# 6x5keyboard_v2_groovy.net
KiCad netlist of a schematic drawn in EAGLE
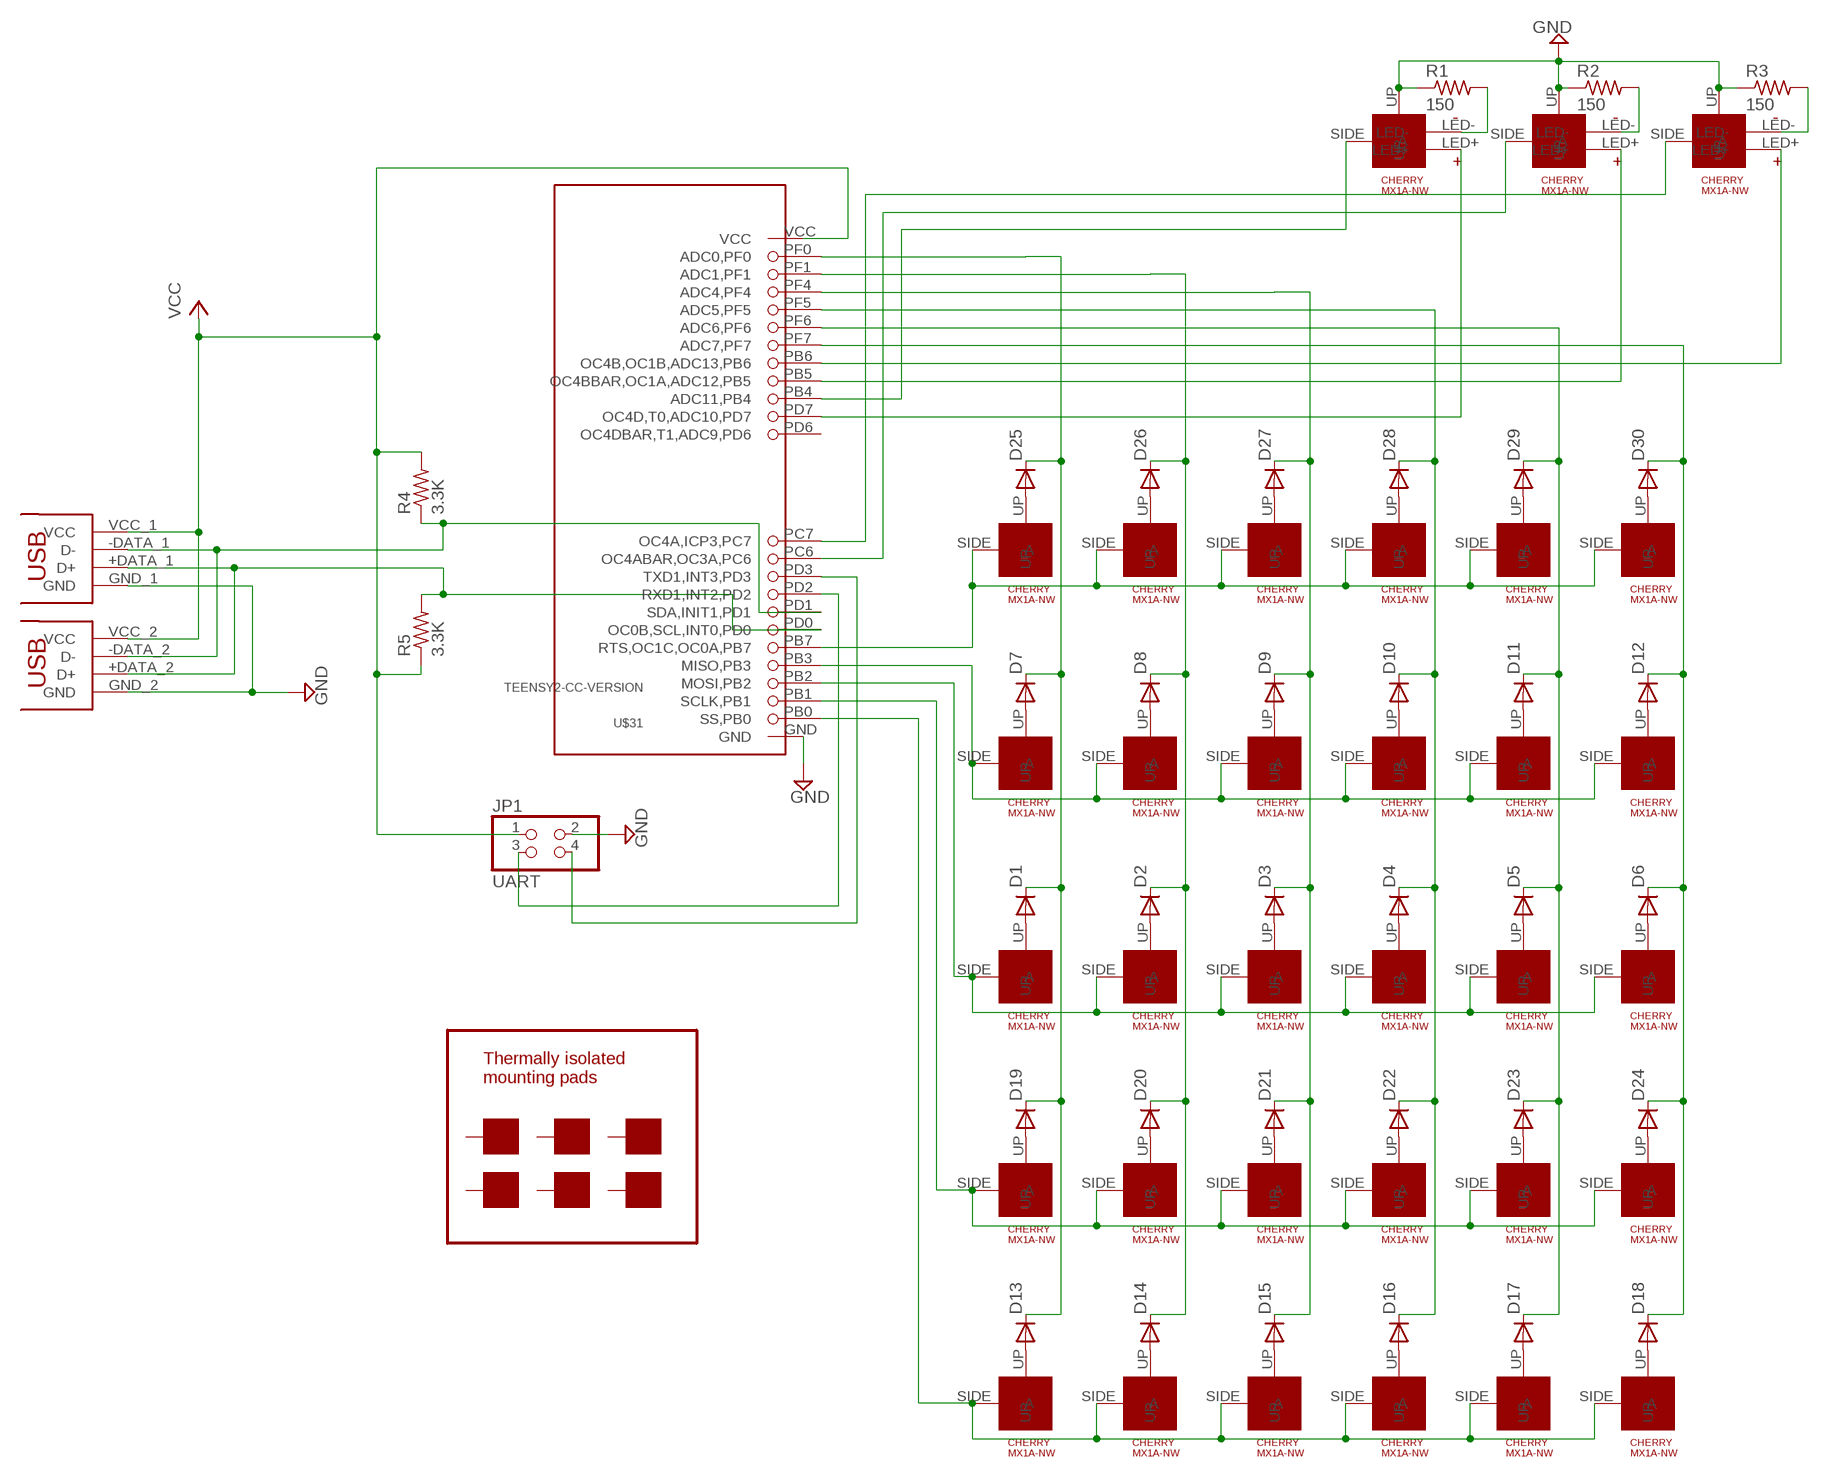
[diagram p0: schematic, sheet 1]

(export (version "E")
  (design (tool "Eeschema 10.0.6"))
  (components
    (comp (ref "D1")
      (value "1N4148DO35-7")
      (footprint "eagle-import:DO35-7")
      (libsource (lib "eagle-import") (part "1N4148DO35-7"))
    )
    (comp (ref "D2")
      (value "1N4148DO35-7")
      (footprint "eagle-import:DO35-7")
      (libsource (lib "eagle-import") (part "1N4148DO35-7"))
    )
    (comp (ref "D3")
      (value "1N4148DO35-7")
      (footprint "eagle-import:DO35-7")
      (libsource (lib "eagle-import") (part "1N4148DO35-7"))
    )
    (comp (ref "D4")
      (value "1N4148DO35-7")
      (footprint "eagle-import:DO35-7")
      (libsource (lib "eagle-import") (part "1N4148DO35-7"))
    )
    (comp (ref "D5")
      (value "1N4148DO35-7")
      (footprint "eagle-import:DO35-7")
      (libsource (lib "eagle-import") (part "1N4148DO35-7"))
    )
    (comp (ref "D6")
      (value "1N4148DO35-7")
      (footprint "eagle-import:DO35-7")
      (libsource (lib "eagle-import") (part "1N4148DO35-7"))
    )
    (comp (ref "D7")
      (value "1N4148DO35-7")
      (footprint "eagle-import:DO35-7")
      (libsource (lib "eagle-import") (part "1N4148DO35-7"))
    )
    (comp (ref "D8")
      (value "1N4148DO35-7")
      (footprint "eagle-import:DO35-7")
      (libsource (lib "eagle-import") (part "1N4148DO35-7"))
    )
    (comp (ref "D9")
      (value "1N4148DO35-7")
      (footprint "eagle-import:DO35-7")
      (libsource (lib "eagle-import") (part "1N4148DO35-7"))
    )
    (comp (ref "D10")
      (value "1N4148DO35-7")
      (footprint "eagle-import:DO35-7")
      (libsource (lib "eagle-import") (part "1N4148DO35-7"))
    )
    (comp (ref "D11")
      (value "1N4148DO35-7")
      (footprint "eagle-import:DO35-7")
      (libsource (lib "eagle-import") (part "1N4148DO35-7"))
    )
    (comp (ref "D12")
      (value "1N4148DO35-7")
      (footprint "eagle-import:DO35-7")
      (libsource (lib "eagle-import") (part "1N4148DO35-7"))
    )
    (comp (ref "D13")
      (value "1N4148DO35-7")
      (footprint "eagle-import:DO35-7")
      (libsource (lib "eagle-import") (part "1N4148DO35-7"))
    )
    (comp (ref "D14")
      (value "1N4148DO35-7")
      (footprint "eagle-import:DO35-7")
      (libsource (lib "eagle-import") (part "1N4148DO35-7"))
    )
    (comp (ref "D15")
      (value "1N4148DO35-7")
      (footprint "eagle-import:DO35-7")
      (libsource (lib "eagle-import") (part "1N4148DO35-7"))
    )
    (comp (ref "D16")
      (value "1N4148DO35-7")
      (footprint "eagle-import:DO35-7")
      (libsource (lib "eagle-import") (part "1N4148DO35-7"))
    )
    (comp (ref "D17")
      (value "1N4148DO35-7")
      (footprint "eagle-import:DO35-7")
      (libsource (lib "eagle-import") (part "1N4148DO35-7"))
    )
    (comp (ref "D18")
      (value "1N4148DO35-7")
      (footprint "eagle-import:DO35-7")
      (libsource (lib "eagle-import") (part "1N4148DO35-7"))
    )
    (comp (ref "D19")
      (value "1N4148DO35-7")
      (footprint "eagle-import:DO35-7")
      (libsource (lib "eagle-import") (part "1N4148DO35-7"))
    )
    (comp (ref "D20")
      (value "1N4148DO35-7")
      (footprint "eagle-import:DO35-7")
      (libsource (lib "eagle-import") (part "1N4148DO35-7"))
    )
    (comp (ref "D21")
      (value "1N4148DO35-7")
      (footprint "eagle-import:DO35-7")
      (libsource (lib "eagle-import") (part "1N4148DO35-7"))
    )
    (comp (ref "D22")
      (value "1N4148DO35-7")
      (footprint "eagle-import:DO35-7")
      (libsource (lib "eagle-import") (part "1N4148DO35-7"))
    )
    (comp (ref "D23")
      (value "1N4148DO35-7")
      (footprint "eagle-import:DO35-7")
      (libsource (lib "eagle-import") (part "1N4148DO35-7"))
    )
    (comp (ref "D24")
      (value "1N4148DO35-7")
      (footprint "eagle-import:DO35-7")
      (libsource (lib "eagle-import") (part "1N4148DO35-7"))
    )
    (comp (ref "D25")
      (value "1N4148DO35-7")
      (footprint "eagle-import:DO35-7")
      (libsource (lib "eagle-import") (part "1N4148DO35-7"))
    )
    (comp (ref "D26")
      (value "1N4148DO35-7")
      (footprint "eagle-import:DO35-7")
      (libsource (lib "eagle-import") (part "1N4148DO35-7"))
    )
    (comp (ref "D27")
      (value "1N4148DO35-7")
      (footprint "eagle-import:DO35-7")
      (libsource (lib "eagle-import") (part "1N4148DO35-7"))
    )
    (comp (ref "D28")
      (value "1N4148DO35-7")
      (footprint "eagle-import:DO35-7")
      (libsource (lib "eagle-import") (part "1N4148DO35-7"))
    )
    (comp (ref "D29")
      (value "1N4148DO35-7")
      (footprint "eagle-import:DO35-7")
      (libsource (lib "eagle-import") (part "1N4148DO35-7"))
    )
    (comp (ref "D30")
      (value "1N4148DO35-7")
      (footprint "eagle-import:DO35-7")
      (libsource (lib "eagle-import") (part "1N4148DO35-7"))
    )
    (comp (ref "JP1")
      (value "UART")
      (footprint "eagle-import:2X02")
      (libsource (lib "eagle-import") (part "PINHD-2X2"))
    )
    (comp (ref "R1")
      (value "150")
      (footprint "eagle-import:0207_10")
      (libsource (lib "eagle-import") (part "R-US_0207/10"))
    )
    (comp (ref "R2")
      (value "150")
      (footprint "eagle-import:0207_10")
      (libsource (lib "eagle-import") (part "R-US_0207/10"))
    )
    (comp (ref "R3")
      (value "150")
      (footprint "eagle-import:0207_10")
      (libsource (lib "eagle-import") (part "R-US_0207/10"))
    )
    (comp (ref "R4")
      (value "3.3K")
      (footprint "eagle-import:0207_10")
      (libsource (lib "eagle-import") (part "resistor_R-US_0207/10"))
    )
    (comp (ref "R5")
      (value "3.3K")
      (footprint "eagle-import:0207_10")
      (libsource (lib "eagle-import") (part "resistor_R-US_0207/10"))
    )
    (comp (ref "U$1")
      (value "CHERRY-MX1A-E1NW")
      (footprint "eagle-import:CHERRYMX-NN")
      (libsource (lib "eagle-import") (part "CHERRY-MX1A-E1NW"))
    )
    (comp (ref "U$2")
      (value "CHERRY-MX1A-E1NW")
      (footprint "eagle-import:CHERRYMX-NN")
      (libsource (lib "eagle-import") (part "CHERRY-MX1A-E1NW"))
    )
    (comp (ref "U$3")
      (value "CHERRY-MX1A-E1NW")
      (footprint "eagle-import:CHERRYMX-NN")
      (libsource (lib "eagle-import") (part "CHERRY-MX1A-E1NW"))
    )
    (comp (ref "U$4")
      (value "CHERRY-MX1A-E1NW")
      (footprint "eagle-import:CHERRYMX-NN")
      (libsource (lib "eagle-import") (part "CHERRY-MX1A-E1NW"))
    )
    (comp (ref "U$5")
      (value "CHERRY-MX1A-E1NW")
      (footprint "eagle-import:CHERRYMX-NN")
      (libsource (lib "eagle-import") (part "CHERRY-MX1A-E1NW"))
    )
    (comp (ref "U$6")
      (value "CHERRY-MX1A-E1NW")
      (footprint "eagle-import:CHERRYMX-NN")
      (libsource (lib "eagle-import") (part "CHERRY-MX1A-E1NW"))
    )
    (comp (ref "U$7")
      (value "CHERRY-MX1A-E1NW")
      (footprint "eagle-import:CHERRYMX-NN")
      (libsource (lib "eagle-import") (part "CHERRY-MX1A-E1NW"))
    )
    (comp (ref "U$8")
      (value "CHERRY-MX1A-E1NW")
      (footprint "eagle-import:CHERRYMX-NN")
      (libsource (lib "eagle-import") (part "CHERRY-MX1A-E1NW"))
    )
    (comp (ref "U$9")
      (value "CHERRY-MX1A-E1NW")
      (footprint "eagle-import:CHERRYMX-NN")
      (libsource (lib "eagle-import") (part "CHERRY-MX1A-E1NW"))
    )
    (comp (ref "U$10")
      (value "CHERRY-MX1A-E1NW")
      (footprint "eagle-import:CHERRYMX-NN")
      (libsource (lib "eagle-import") (part "CHERRY-MX1A-E1NW"))
    )
    (comp (ref "U$11")
      (value "CHERRY-MX1A-E1NW")
      (footprint "eagle-import:CHERRYMX-NN")
      (libsource (lib "eagle-import") (part "CHERRY-MX1A-E1NW"))
    )
    (comp (ref "U$12")
      (value "CHERRY-MX1A-E1NW")
      (footprint "eagle-import:CHERRYMX-NN")
      (libsource (lib "eagle-import") (part "CHERRY-MX1A-E1NW"))
    )
    (comp (ref "U$13")
      (value "CHERRY-MX1A-E1NW")
      (footprint "eagle-import:CHERRYMX-NN")
      (libsource (lib "eagle-import") (part "CHERRY-MX1A-E1NW"))
    )
    (comp (ref "U$14")
      (value "CHERRY-MX1A-E1NW")
      (footprint "eagle-import:CHERRYMX-NN")
      (libsource (lib "eagle-import") (part "CHERRY-MX1A-E1NW"))
    )
    (comp (ref "U$15")
      (value "CHERRY-MX1A-E1NW")
      (footprint "eagle-import:CHERRYMX-NN")
      (libsource (lib "eagle-import") (part "CHERRY-MX1A-E1NW"))
    )
    (comp (ref "U$16")
      (value "CHERRY-MX1A-E1NW")
      (footprint "eagle-import:CHERRYMX-NN")
      (libsource (lib "eagle-import") (part "CHERRY-MX1A-E1NW"))
    )
    (comp (ref "U$17")
      (value "CHERRY-MX1A-E1NW")
      (footprint "eagle-import:CHERRYMX-NN")
      (libsource (lib "eagle-import") (part "CHERRY-MX1A-E1NW"))
    )
    (comp (ref "U$18")
      (value "CHERRY-MX1A-E1NW")
      (footprint "eagle-import:CHERRYMX-NN")
      (libsource (lib "eagle-import") (part "CHERRY-MX1A-E1NW"))
    )
    (comp (ref "U$19")
      (value "CHERRY-MX1A-E1NW")
      (footprint "eagle-import:CHERRYMX-NN")
      (libsource (lib "eagle-import") (part "CHERRY-MX1A-E1NW"))
    )
    (comp (ref "U$20")
      (value "CHERRY-MX1A-E1NW")
      (footprint "eagle-import:CHERRYMX-NN")
      (libsource (lib "eagle-import") (part "CHERRY-MX1A-E1NW"))
    )
    (comp (ref "U$21")
      (value "CHERRY-MX1A-E1NW")
      (footprint "eagle-import:CHERRYMX-NN")
      (libsource (lib "eagle-import") (part "CHERRY-MX1A-E1NW"))
    )
    (comp (ref "U$22")
      (value "CHERRY-MX1A-E1NW")
      (footprint "eagle-import:CHERRYMX-NN")
      (libsource (lib "eagle-import") (part "CHERRY-MX1A-E1NW"))
    )
    (comp (ref "U$23")
      (value "CHERRY-MX1A-E1NW")
      (footprint "eagle-import:CHERRYMX-NN")
      (libsource (lib "eagle-import") (part "CHERRY-MX1A-E1NW"))
    )
    (comp (ref "U$24")
      (value "CHERRY-MX1A-E1NW")
      (footprint "eagle-import:CHERRYMX-NN")
      (libsource (lib "eagle-import") (part "CHERRY-MX1A-E1NW"))
    )
    (comp (ref "U$25")
      (value "CHERRY-MX1A-E1NW")
      (footprint "eagle-import:CHERRYMX-NN")
      (libsource (lib "eagle-import") (part "CHERRY-MX1A-E1NW"))
    )
    (comp (ref "U$26")
      (value "CHERRY-MX1A-E1NW")
      (footprint "eagle-import:CHERRYMX-NN")
      (libsource (lib "eagle-import") (part "CHERRY-MX1A-E1NW"))
    )
    (comp (ref "U$27")
      (value "CHERRY-MX1A-E1NW")
      (footprint "eagle-import:CHERRYMX-NN")
      (libsource (lib "eagle-import") (part "CHERRY-MX1A-E1NW"))
    )
    (comp (ref "U$28")
      (value "CHERRY-MX1A-E1NW")
      (footprint "eagle-import:CHERRYMX-NN")
      (libsource (lib "eagle-import") (part "CHERRY-MX1A-E1NW"))
    )
    (comp (ref "U$29")
      (value "CHERRY-MX1A-E1NW")
      (footprint "eagle-import:CHERRYMX-NN")
      (libsource (lib "eagle-import") (part "CHERRY-MX1A-E1NW"))
    )
    (comp (ref "U$30")
      (value "CHERRY-MX1A-E1NW")
      (footprint "eagle-import:CHERRYMX-NN")
      (libsource (lib "eagle-import") (part "CHERRY-MX1A-E1NW"))
    )
    (comp (ref "U$31")
      (value "TEENSY2-CC-VERSION")
      (footprint "eagle-import:TEENSY2")
      (libsource (lib "eagle-import") (part "TEENSY2-CC-VERSION"))
    )
    (comp (ref "U$32")
      (value "CHERRY-MX1A-E1NW-LED")
      (footprint "eagle-import:CHERRYMX-NN-LED")
      (libsource (lib "eagle-import") (part "CHERRY-MX1A-E1NW-LED"))
    )
    (comp (ref "U$33")
      (value "CHERRY-MX1A-E1NW-LED")
      (footprint "eagle-import:CHERRYMX-NN-LED")
      (libsource (lib "eagle-import") (part "CHERRY-MX1A-E1NW-LED"))
    )
    (comp (ref "U$34")
      (value "CHERRY-MX1A-E1NW-LED")
      (footprint "eagle-import:CHERRYMX-NN-LED")
      (libsource (lib "eagle-import") (part "CHERRY-MX1A-E1NW-LED"))
    )
    (comp (ref "U$35")
      (value "DUAL-USB-A")
      (footprint "eagle-import:DUAL-USB-A")
      (libsource (lib "eagle-import") (part "DUAL-USB-A"))
    )
    (comp (ref "U$36")
      (value "MOUNTING-PAD")
      (footprint "eagle-import:MOUNTING-PAD")
      (libsource (lib "eagle-import") (part "MOUNTING-PAD"))
    )
    (comp (ref "U$37")
      (value "MOUNTING-PAD")
      (footprint "eagle-import:MOUNTING-PAD")
      (libsource (lib "eagle-import") (part "MOUNTING-PAD"))
    )
    (comp (ref "U$38")
      (value "MOUNTING-PAD")
      (footprint "eagle-import:MOUNTING-PAD")
      (libsource (lib "eagle-import") (part "MOUNTING-PAD"))
    )
    (comp (ref "U$39")
      (value "MOUNTING-PAD")
      (footprint "eagle-import:MOUNTING-PAD")
      (libsource (lib "eagle-import") (part "MOUNTING-PAD"))
    )
    (comp (ref "U$40")
      (value "MOUNTING-PAD")
      (footprint "eagle-import:MOUNTING-PAD")
      (libsource (lib "eagle-import") (part "MOUNTING-PAD"))
    )
    (comp (ref "U$41")
      (value "MOUNTING-PAD")
      (footprint "eagle-import:MOUNTING-PAD")
      (libsource (lib "eagle-import") (part "MOUNTING-PAD"))
    )
  )
  (nets
    (net (code "1") (name "GND") (class "Default")
      (node (ref "JP1") (pin "2") (pinfunction "2_2") (pintype "passive"))
      (node (ref "R1") (pin "1") (pinfunction "1_1") (pintype "passive"))
      (node (ref "R2") (pin "1") (pinfunction "1_1") (pintype "passive"))
      (node (ref "R3") (pin "1") (pinfunction "1_1") (pintype "passive"))
      (node (ref "U$31") (pin "GND") (pinfunction "GND_GND") (pintype "power_in"))
      (node (ref "U$32") (pin "UP") (pinfunction "UP_UP") (pintype "bidirectional"))
      (node (ref "U$33") (pin "UP") (pinfunction "UP_UP") (pintype "bidirectional"))
      (node (ref "U$34") (pin "UP") (pinfunction "UP_UP") (pintype "bidirectional"))
      (node (ref "U$35") (pin "GND_1") (pinfunction "GND_GND_1") (pintype "bidirectional"))
      (node (ref "U$35") (pin "GND_2") (pinfunction "GND_GND_2") (pintype "bidirectional"))
    )
    (net (code "2") (name "Net-(D1-PadA)") (class "Default")
      (node (ref "D1") (pin "A") (pinfunction "A_A") (pintype "passive"))
      (node (ref "U$2") (pin "UP") (pinfunction "UP_UP") (pintype "bidirectional"))
    )
    (net (code "3") (name "Net-(D2-PadA)") (class "Default")
      (node (ref "D2") (pin "A") (pinfunction "A_A") (pintype "passive"))
      (node (ref "U$1") (pin "UP") (pinfunction "UP_UP") (pintype "bidirectional"))
    )
    (net (code "4") (name "Net-(D3-PadA)") (class "Default")
      (node (ref "D3") (pin "A") (pinfunction "A_A") (pintype "passive"))
      (node (ref "U$3") (pin "UP") (pinfunction "UP_UP") (pintype "bidirectional"))
    )
    (net (code "5") (name "Net-(D4-PadA)") (class "Default")
      (node (ref "D4") (pin "A") (pinfunction "A_A") (pintype "passive"))
      (node (ref "U$4") (pin "UP") (pinfunction "UP_UP") (pintype "bidirectional"))
    )
    (net (code "6") (name "Net-(D5-PadA)") (class "Default")
      (node (ref "D5") (pin "A") (pinfunction "A_A") (pintype "passive"))
      (node (ref "U$5") (pin "UP") (pinfunction "UP_UP") (pintype "bidirectional"))
    )
    (net (code "7") (name "Net-(D6-PadA)") (class "Default")
      (node (ref "D6") (pin "A") (pinfunction "A_A") (pintype "passive"))
      (node (ref "U$6") (pin "UP") (pinfunction "UP_UP") (pintype "bidirectional"))
    )
    (net (code "8") (name "Net-(D7-PadA)") (class "Default")
      (node (ref "D7") (pin "A") (pinfunction "A_A") (pintype "passive"))
      (node (ref "U$7") (pin "UP") (pinfunction "UP_UP") (pintype "bidirectional"))
    )
    (net (code "9") (name "Net-(D8-PadA)") (class "Default")
      (node (ref "D8") (pin "A") (pinfunction "A_A") (pintype "passive"))
      (node (ref "U$8") (pin "UP") (pinfunction "UP_UP") (pintype "bidirectional"))
    )
    (net (code "10") (name "Net-(D9-PadA)") (class "Default")
      (node (ref "D9") (pin "A") (pinfunction "A_A") (pintype "passive"))
      (node (ref "U$9") (pin "UP") (pinfunction "UP_UP") (pintype "bidirectional"))
    )
    (net (code "11") (name "Net-(D10-PadA)") (class "Default")
      (node (ref "D10") (pin "A") (pinfunction "A_A") (pintype "passive"))
      (node (ref "U$10") (pin "UP") (pinfunction "UP_UP") (pintype "bidirectional"))
    )
    (net (code "12") (name "Net-(D11-PadA)") (class "Default")
      (node (ref "D11") (pin "A") (pinfunction "A_A") (pintype "passive"))
      (node (ref "U$11") (pin "UP") (pinfunction "UP_UP") (pintype "bidirectional"))
    )
    (net (code "13") (name "Net-(D12-PadA)") (class "Default")
      (node (ref "D12") (pin "A") (pinfunction "A_A") (pintype "passive"))
      (node (ref "U$12") (pin "UP") (pinfunction "UP_UP") (pintype "bidirectional"))
    )
    (net (code "14") (name "Net-(D13-PadA)") (class "Default")
      (node (ref "D13") (pin "A") (pinfunction "A_A") (pintype "passive"))
      (node (ref "U$13") (pin "UP") (pinfunction "UP_UP") (pintype "bidirectional"))
    )
    (net (code "15") (name "Net-(D14-PadA)") (class "Default")
      (node (ref "D14") (pin "A") (pinfunction "A_A") (pintype "passive"))
      (node (ref "U$14") (pin "UP") (pinfunction "UP_UP") (pintype "bidirectional"))
    )
    (net (code "16") (name "Net-(D15-PadA)") (class "Default")
      (node (ref "D15") (pin "A") (pinfunction "A_A") (pintype "passive"))
      (node (ref "U$15") (pin "UP") (pinfunction "UP_UP") (pintype "bidirectional"))
    )
    (net (code "17") (name "Net-(D16-PadA)") (class "Default")
      (node (ref "D16") (pin "A") (pinfunction "A_A") (pintype "passive"))
      (node (ref "U$16") (pin "UP") (pinfunction "UP_UP") (pintype "bidirectional"))
    )
    (net (code "18") (name "Net-(D17-PadA)") (class "Default")
      (node (ref "D17") (pin "A") (pinfunction "A_A") (pintype "passive"))
      (node (ref "U$17") (pin "UP") (pinfunction "UP_UP") (pintype "bidirectional"))
    )
    (net (code "19") (name "Net-(D18-PadA)") (class "Default")
      (node (ref "D18") (pin "A") (pinfunction "A_A") (pintype "passive"))
      (node (ref "U$18") (pin "UP") (pinfunction "UP_UP") (pintype "bidirectional"))
    )
    (net (code "20") (name "Net-(D19-PadA)") (class "Default")
      (node (ref "D19") (pin "A") (pinfunction "A_A") (pintype "passive"))
      (node (ref "U$19") (pin "UP") (pinfunction "UP_UP") (pintype "bidirectional"))
    )
    (net (code "21") (name "Net-(D20-PadA)") (class "Default")
      (node (ref "D20") (pin "A") (pinfunction "A_A") (pintype "passive"))
      (node (ref "U$20") (pin "UP") (pinfunction "UP_UP") (pintype "bidirectional"))
    )
    (net (code "22") (name "Net-(D21-PadA)") (class "Default")
      (node (ref "D21") (pin "A") (pinfunction "A_A") (pintype "passive"))
      (node (ref "U$21") (pin "UP") (pinfunction "UP_UP") (pintype "bidirectional"))
    )
    (net (code "23") (name "Net-(D22-PadA)") (class "Default")
      (node (ref "D22") (pin "A") (pinfunction "A_A") (pintype "passive"))
      (node (ref "U$22") (pin "UP") (pinfunction "UP_UP") (pintype "bidirectional"))
    )
    (net (code "24") (name "Net-(D23-PadA)") (class "Default")
      (node (ref "D23") (pin "A") (pinfunction "A_A") (pintype "passive"))
      (node (ref "U$23") (pin "UP") (pinfunction "UP_UP") (pintype "bidirectional"))
    )
    (net (code "25") (name "Net-(D24-PadA)") (class "Default")
      (node (ref "D24") (pin "A") (pinfunction "A_A") (pintype "passive"))
      (node (ref "U$24") (pin "UP") (pinfunction "UP_UP") (pintype "bidirectional"))
    )
    (net (code "26") (name "Net-(D25-PadA)") (class "Default")
      (node (ref "D25") (pin "A") (pinfunction "A_A") (pintype "passive"))
      (node (ref "U$25") (pin "UP") (pinfunction "UP_UP") (pintype "bidirectional"))
    )
    (net (code "27") (name "Net-(D26-PadA)") (class "Default")
      (node (ref "D26") (pin "A") (pinfunction "A_A") (pintype "passive"))
      (node (ref "U$26") (pin "UP") (pinfunction "UP_UP") (pintype "bidirectional"))
    )
    (net (code "28") (name "Net-(D27-PadA)") (class "Default")
      (node (ref "D27") (pin "A") (pinfunction "A_A") (pintype "passive"))
      (node (ref "U$27") (pin "UP") (pinfunction "UP_UP") (pintype "bidirectional"))
    )
    (net (code "29") (name "Net-(D28-PadA)") (class "Default")
      (node (ref "D28") (pin "A") (pinfunction "A_A") (pintype "passive"))
      (node (ref "U$28") (pin "UP") (pinfunction "UP_UP") (pintype "bidirectional"))
    )
    (net (code "30") (name "Net-(D29-PadA)") (class "Default")
      (node (ref "D29") (pin "A") (pinfunction "A_A") (pintype "passive"))
      (node (ref "U$29") (pin "UP") (pinfunction "UP_UP") (pintype "bidirectional"))
    )
    (net (code "31") (name "Net-(D30-PadA)") (class "Default")
      (node (ref "D30") (pin "A") (pinfunction "A_A") (pintype "passive"))
      (node (ref "U$30") (pin "UP") (pinfunction "UP_UP") (pintype "bidirectional"))
    )
    (net (code "32") (name "Net-(R1-Pad2)") (class "Default")
      (node (ref "R1") (pin "2") (pinfunction "2_2") (pintype "passive"))
      (node (ref "U$32") (pin "LED-") (pinfunction "LED-_LED-") (pintype "bidirectional"))
    )
    (net (code "33") (name "Net-(R2-Pad2)") (class "Default")
      (node (ref "R2") (pin "2") (pinfunction "2_2") (pintype "passive"))
      (node (ref "U$33") (pin "LED-") (pinfunction "LED-_LED-") (pintype "bidirectional"))
    )
    (net (code "34") (name "Net-(R3-Pad2)") (class "Default")
      (node (ref "R3") (pin "2") (pinfunction "2_2") (pintype "passive"))
      (node (ref "U$34") (pin "LED-") (pinfunction "LED-_LED-") (pintype "bidirectional"))
    )
    (net (code "35") (name "Net-(U$1-A)") (class "Default")
      (node (ref "U$1") (pin "SIDE") (pinfunction "A_SIDE") (pintype "bidirectional"))
      (node (ref "U$2") (pin "SIDE") (pinfunction "A_SIDE") (pintype "bidirectional"))
      (node (ref "U$3") (pin "SIDE") (pinfunction "A_SIDE") (pintype "bidirectional"))
      (node (ref "U$31") (pin "PB2") (pinfunction "MOSI,PB2_PB2") (pintype "bidirectional"))
      (node (ref "U$4") (pin "SIDE") (pinfunction "A_SIDE") (pintype "bidirectional"))
      (node (ref "U$5") (pin "SIDE") (pinfunction "A_SIDE") (pintype "bidirectional"))
      (node (ref "U$6") (pin "SIDE") (pinfunction "A_SIDE") (pintype "bidirectional"))
    )
    (net (code "36") (name "Net-(U$10-A)") (class "Default")
      (node (ref "U$10") (pin "SIDE") (pinfunction "A_SIDE") (pintype "bidirectional"))
      (node (ref "U$11") (pin "SIDE") (pinfunction "A_SIDE") (pintype "bidirectional"))
      (node (ref "U$12") (pin "SIDE") (pinfunction "A_SIDE") (pintype "bidirectional"))
      (node (ref "U$31") (pin "PB3") (pinfunction "MISO,PB3_PB3") (pintype "bidirectional"))
      (node (ref "U$7") (pin "SIDE") (pinfunction "A_SIDE") (pintype "bidirectional"))
      (node (ref "U$8") (pin "SIDE") (pinfunction "A_SIDE") (pintype "bidirectional"))
      (node (ref "U$9") (pin "SIDE") (pinfunction "A_SIDE") (pintype "bidirectional"))
    )
    (net (code "37") (name "Net-(U$13-A)") (class "Default")
      (node (ref "U$13") (pin "SIDE") (pinfunction "A_SIDE") (pintype "bidirectional"))
      (node (ref "U$14") (pin "SIDE") (pinfunction "A_SIDE") (pintype "bidirectional"))
      (node (ref "U$15") (pin "SIDE") (pinfunction "A_SIDE") (pintype "bidirectional"))
      (node (ref "U$16") (pin "SIDE") (pinfunction "A_SIDE") (pintype "bidirectional"))
      (node (ref "U$17") (pin "SIDE") (pinfunction "A_SIDE") (pintype "bidirectional"))
      (node (ref "U$18") (pin "SIDE") (pinfunction "A_SIDE") (pintype "bidirectional"))
      (node (ref "U$31") (pin "PB0") (pinfunction "SS,PB0_PB0") (pintype "bidirectional"))
    )
    (net (code "38") (name "Net-(U$19-A)") (class "Default")
      (node (ref "U$19") (pin "SIDE") (pinfunction "A_SIDE") (pintype "bidirectional"))
      (node (ref "U$20") (pin "SIDE") (pinfunction "A_SIDE") (pintype "bidirectional"))
      (node (ref "U$21") (pin "SIDE") (pinfunction "A_SIDE") (pintype "bidirectional"))
      (node (ref "U$22") (pin "SIDE") (pinfunction "A_SIDE") (pintype "bidirectional"))
      (node (ref "U$23") (pin "SIDE") (pinfunction "A_SIDE") (pintype "bidirectional"))
      (node (ref "U$24") (pin "SIDE") (pinfunction "A_SIDE") (pintype "bidirectional"))
      (node (ref "U$31") (pin "PB1") (pinfunction "SCLK,PB1_PB1") (pintype "bidirectional"))
    )
    (net (code "39") (name "Net-(U$25-A)") (class "Default")
      (node (ref "U$25") (pin "SIDE") (pinfunction "A_SIDE") (pintype "bidirectional"))
      (node (ref "U$26") (pin "SIDE") (pinfunction "A_SIDE") (pintype "bidirectional"))
      (node (ref "U$27") (pin "SIDE") (pinfunction "A_SIDE") (pintype "bidirectional"))
      (node (ref "U$28") (pin "SIDE") (pinfunction "A_SIDE") (pintype "bidirectional"))
      (node (ref "U$29") (pin "SIDE") (pinfunction "A_SIDE") (pintype "bidirectional"))
      (node (ref "U$30") (pin "SIDE") (pinfunction "A_SIDE") (pintype "bidirectional"))
      (node (ref "U$31") (pin "PB7") (pinfunction "RTS,OC1C,OC0A,PB7_PB7") (pintype "bidirectional"))
    )
    (net (code "40") (name "Net-(U$31-ADC0,PF0)") (class "Default")
      (node (ref "D1") (pin "C") (pinfunction "C_C") (pintype "passive"))
      (node (ref "D13") (pin "C") (pinfunction "C_C") (pintype "passive"))
      (node (ref "D19") (pin "C") (pinfunction "C_C") (pintype "passive"))
      (node (ref "D25") (pin "C") (pinfunction "C_C") (pintype "passive"))
      (node (ref "D7") (pin "C") (pinfunction "C_C") (pintype "passive"))
      (node (ref "U$31") (pin "PF0") (pinfunction "ADC0,PF0_PF0") (pintype "bidirectional"))
    )
    (net (code "41") (name "Net-(U$31-ADC1,PF1)") (class "Default")
      (node (ref "D14") (pin "C") (pinfunction "C_C") (pintype "passive"))
      (node (ref "D2") (pin "C") (pinfunction "C_C") (pintype "passive"))
      (node (ref "D20") (pin "C") (pinfunction "C_C") (pintype "passive"))
      (node (ref "D26") (pin "C") (pinfunction "C_C") (pintype "passive"))
      (node (ref "D8") (pin "C") (pinfunction "C_C") (pintype "passive"))
      (node (ref "U$31") (pin "PF1") (pinfunction "ADC1,PF1_PF1") (pintype "bidirectional"))
    )
    (net (code "42") (name "Net-(U$31-ADC4,PF4)") (class "Default")
      (node (ref "D15") (pin "C") (pinfunction "C_C") (pintype "passive"))
      (node (ref "D21") (pin "C") (pinfunction "C_C") (pintype "passive"))
      (node (ref "D27") (pin "C") (pinfunction "C_C") (pintype "passive"))
      (node (ref "D3") (pin "C") (pinfunction "C_C") (pintype "passive"))
      (node (ref "D9") (pin "C") (pinfunction "C_C") (pintype "passive"))
      (node (ref "U$31") (pin "PF4") (pinfunction "ADC4,PF4_PF4") (pintype "bidirectional"))
    )
    (net (code "43") (name "Net-(U$31-ADC5,PF5)") (class "Default")
      (node (ref "D10") (pin "C") (pinfunction "C_C") (pintype "passive"))
      (node (ref "D16") (pin "C") (pinfunction "C_C") (pintype "passive"))
      (node (ref "D22") (pin "C") (pinfunction "C_C") (pintype "passive"))
      (node (ref "D28") (pin "C") (pinfunction "C_C") (pintype "passive"))
      (node (ref "D4") (pin "C") (pinfunction "C_C") (pintype "passive"))
      (node (ref "U$31") (pin "PF5") (pinfunction "ADC5,PF5_PF5") (pintype "bidirectional"))
    )
    (net (code "44") (name "Net-(U$31-ADC6,PF6)") (class "Default")
      (node (ref "D11") (pin "C") (pinfunction "C_C") (pintype "passive"))
      (node (ref "D17") (pin "C") (pinfunction "C_C") (pintype "passive"))
      (node (ref "D23") (pin "C") (pinfunction "C_C") (pintype "passive"))
      (node (ref "D29") (pin "C") (pinfunction "C_C") (pintype "passive"))
      (node (ref "D5") (pin "C") (pinfunction "C_C") (pintype "passive"))
      (node (ref "U$31") (pin "PF6") (pinfunction "ADC6,PF6_PF6") (pintype "bidirectional"))
    )
    (net (code "45") (name "Net-(U$31-ADC7,PF7)") (class "Default")
      (node (ref "D12") (pin "C") (pinfunction "C_C") (pintype "passive"))
      (node (ref "D18") (pin "C") (pinfunction "C_C") (pintype "passive"))
      (node (ref "D24") (pin "C") (pinfunction "C_C") (pintype "passive"))
      (node (ref "D30") (pin "C") (pinfunction "C_C") (pintype "passive"))
      (node (ref "D6") (pin "C") (pinfunction "C_C") (pintype "passive"))
      (node (ref "U$31") (pin "PF7") (pinfunction "ADC7,PF7_PF7") (pintype "bidirectional"))
    )
    (net (code "46") (name "Net-(U$31-ADC11,PB4)") (class "Default")
      (node (ref "U$31") (pin "PB4") (pinfunction "ADC11,PB4_PB4") (pintype "bidirectional"))
      (node (ref "U$32") (pin "SIDE") (pinfunction "A_SIDE") (pintype "bidirectional"))
    )
    (net (code "47") (name "Net-(U$31-OC0B,SCL,INT0,PD0)") (class "Default")
      (node (ref "R5") (pin "2") (pinfunction "2_2") (pintype "passive"))
      (node (ref "U$31") (pin "PD0") (pinfunction "OC0B,SCL,INT0,PD0_PD0") (pintype "bidirectional"))
      (node (ref "U$35") (pin "+DATA_1") (pinfunction "D+_+DATA_1") (pintype "bidirectional"))
      (node (ref "U$35") (pin "+DATA_2") (pinfunction "D+_+DATA_2") (pintype "bidirectional"))
    )
    (net (code "48") (name "Net-(U$31-OC4A,ICP3,PC7)") (class "Default")
      (node (ref "U$31") (pin "PC7") (pinfunction "OC4A,ICP3,PC7_PC7") (pintype "bidirectional"))
      (node (ref "U$34") (pin "SIDE") (pinfunction "A_SIDE") (pintype "bidirectional"))
    )
    (net (code "49") (name "Net-(U$31-OC4ABAR,OC3A,PC6)") (class "Default")
      (node (ref "U$31") (pin "PC6") (pinfunction "OC4ABAR,OC3A,PC6_PC6") (pintype "bidirectional"))
      (node (ref "U$33") (pin "SIDE") (pinfunction "A_SIDE") (pintype "bidirectional"))
    )
    (net (code "50") (name "Net-(U$31-OC4B,OC1B,ADC13,PB6)") (class "Default")
      (node (ref "U$31") (pin "PB6") (pinfunction "OC4B,OC1B,ADC13,PB6_PB6") (pintype "bidirectional"))
      (node (ref "U$34") (pin "LED+") (pinfunction "LED+_LED+") (pintype "bidirectional"))
    )
    (net (code "51") (name "Net-(U$31-OC4BBAR,OC1A,ADC12,PB5)") (class "Default")
      (node (ref "U$31") (pin "PB5") (pinfunction "OC4BBAR,OC1A,ADC12,PB5_PB5") (pintype "bidirectional"))
      (node (ref "U$33") (pin "LED+") (pinfunction "LED+_LED+") (pintype "bidirectional"))
    )
    (net (code "52") (name "Net-(U$31-OC4D,T0,ADC10,PD7)") (class "Default")
      (node (ref "U$31") (pin "PD7") (pinfunction "OC4D,T0,ADC10,PD7_PD7") (pintype "bidirectional"))
      (node (ref "U$32") (pin "LED+") (pinfunction "LED+_LED+") (pintype "bidirectional"))
    )
    (net (code "53") (name "Net-(U$31-RXD1,INT2,PD2)") (class "Default")
      (node (ref "JP1") (pin "3") (pinfunction "3_3") (pintype "passive"))
      (node (ref "U$31") (pin "PD2") (pinfunction "RXD1,INT2,PD2_PD2") (pintype "bidirectional"))
    )
    (net (code "54") (name "Net-(U$31-SDA,INIT1,PD1)") (class "Default")
      (node (ref "R4") (pin "1") (pinfunction "1_1") (pintype "passive"))
      (node (ref "U$31") (pin "PD1") (pinfunction "SDA,INIT1,PD1_PD1") (pintype "bidirectional"))
      (node (ref "U$35") (pin "-DATA_1") (pinfunction "D-_-DATA_1") (pintype "bidirectional"))
      (node (ref "U$35") (pin "-DATA_2") (pinfunction "D-_-DATA_2") (pintype "bidirectional"))
    )
    (net (code "55") (name "Net-(U$31-TXD1,INT3,PD3)") (class "Default")
      (node (ref "JP1") (pin "4") (pinfunction "4_4") (pintype "passive"))
      (node (ref "U$31") (pin "PD3") (pinfunction "TXD1,INT3,PD3_PD3") (pintype "bidirectional"))
    )
    (net (code "56") (name "VCC") (class "Default")
      (node (ref "JP1") (pin "1") (pinfunction "1_1") (pintype "passive"))
      (node (ref "R4") (pin "2") (pinfunction "2_2") (pintype "passive"))
      (node (ref "R5") (pin "1") (pinfunction "1_1") (pintype "passive"))
      (node (ref "U$31") (pin "VCC") (pinfunction "VCC_VCC") (pintype "power_in"))
      (node (ref "U$35") (pin "VCC_1") (pinfunction "VCC_VCC_1") (pintype "bidirectional"))
      (node (ref "U$35") (pin "VCC_2") (pinfunction "VCC_VCC_2") (pintype "bidirectional"))
    )
    (net (code "57") (name "unconnected-(U$31-OC4DBAR,T1,ADC9,PD6-PadPD6)") (class "Default")
      (node (ref "U$31") (pin "PD6") (pinfunction "OC4DBAR,T1,ADC9,PD6_PD6") (pintype "bidirectional"))
    )
    (net (code "58") (name "unconnected-(U$36-PadP$1)") (class "Default")
      (node (ref "U$36") (pin "P$1") (pinfunction "P$1_P$1") (pintype "no_connect"))
    )
    (net (code "59") (name "unconnected-(U$37-PadP$1)") (class "Default")
      (node (ref "U$37") (pin "P$1") (pinfunction "P$1_P$1") (pintype "no_connect"))
    )
    (net (code "60") (name "unconnected-(U$38-PadP$1)") (class "Default")
      (node (ref "U$38") (pin "P$1") (pinfunction "P$1_P$1") (pintype "no_connect"))
    )
    (net (code "61") (name "unconnected-(U$39-PadP$1)") (class "Default")
      (node (ref "U$39") (pin "P$1") (pinfunction "P$1_P$1") (pintype "no_connect"))
    )
    (net (code "62") (name "unconnected-(U$40-PadP$1)") (class "Default")
      (node (ref "U$40") (pin "P$1") (pinfunction "P$1_P$1") (pintype "no_connect"))
    )
    (net (code "63") (name "unconnected-(U$41-PadP$1)") (class "Default")
      (node (ref "U$41") (pin "P$1") (pinfunction "P$1_P$1") (pintype "no_connect"))
    )
  )
)
